# Pow-OR_v13-SFE-Pi.net
KiCad netlist of a schematic drawn in EAGLE
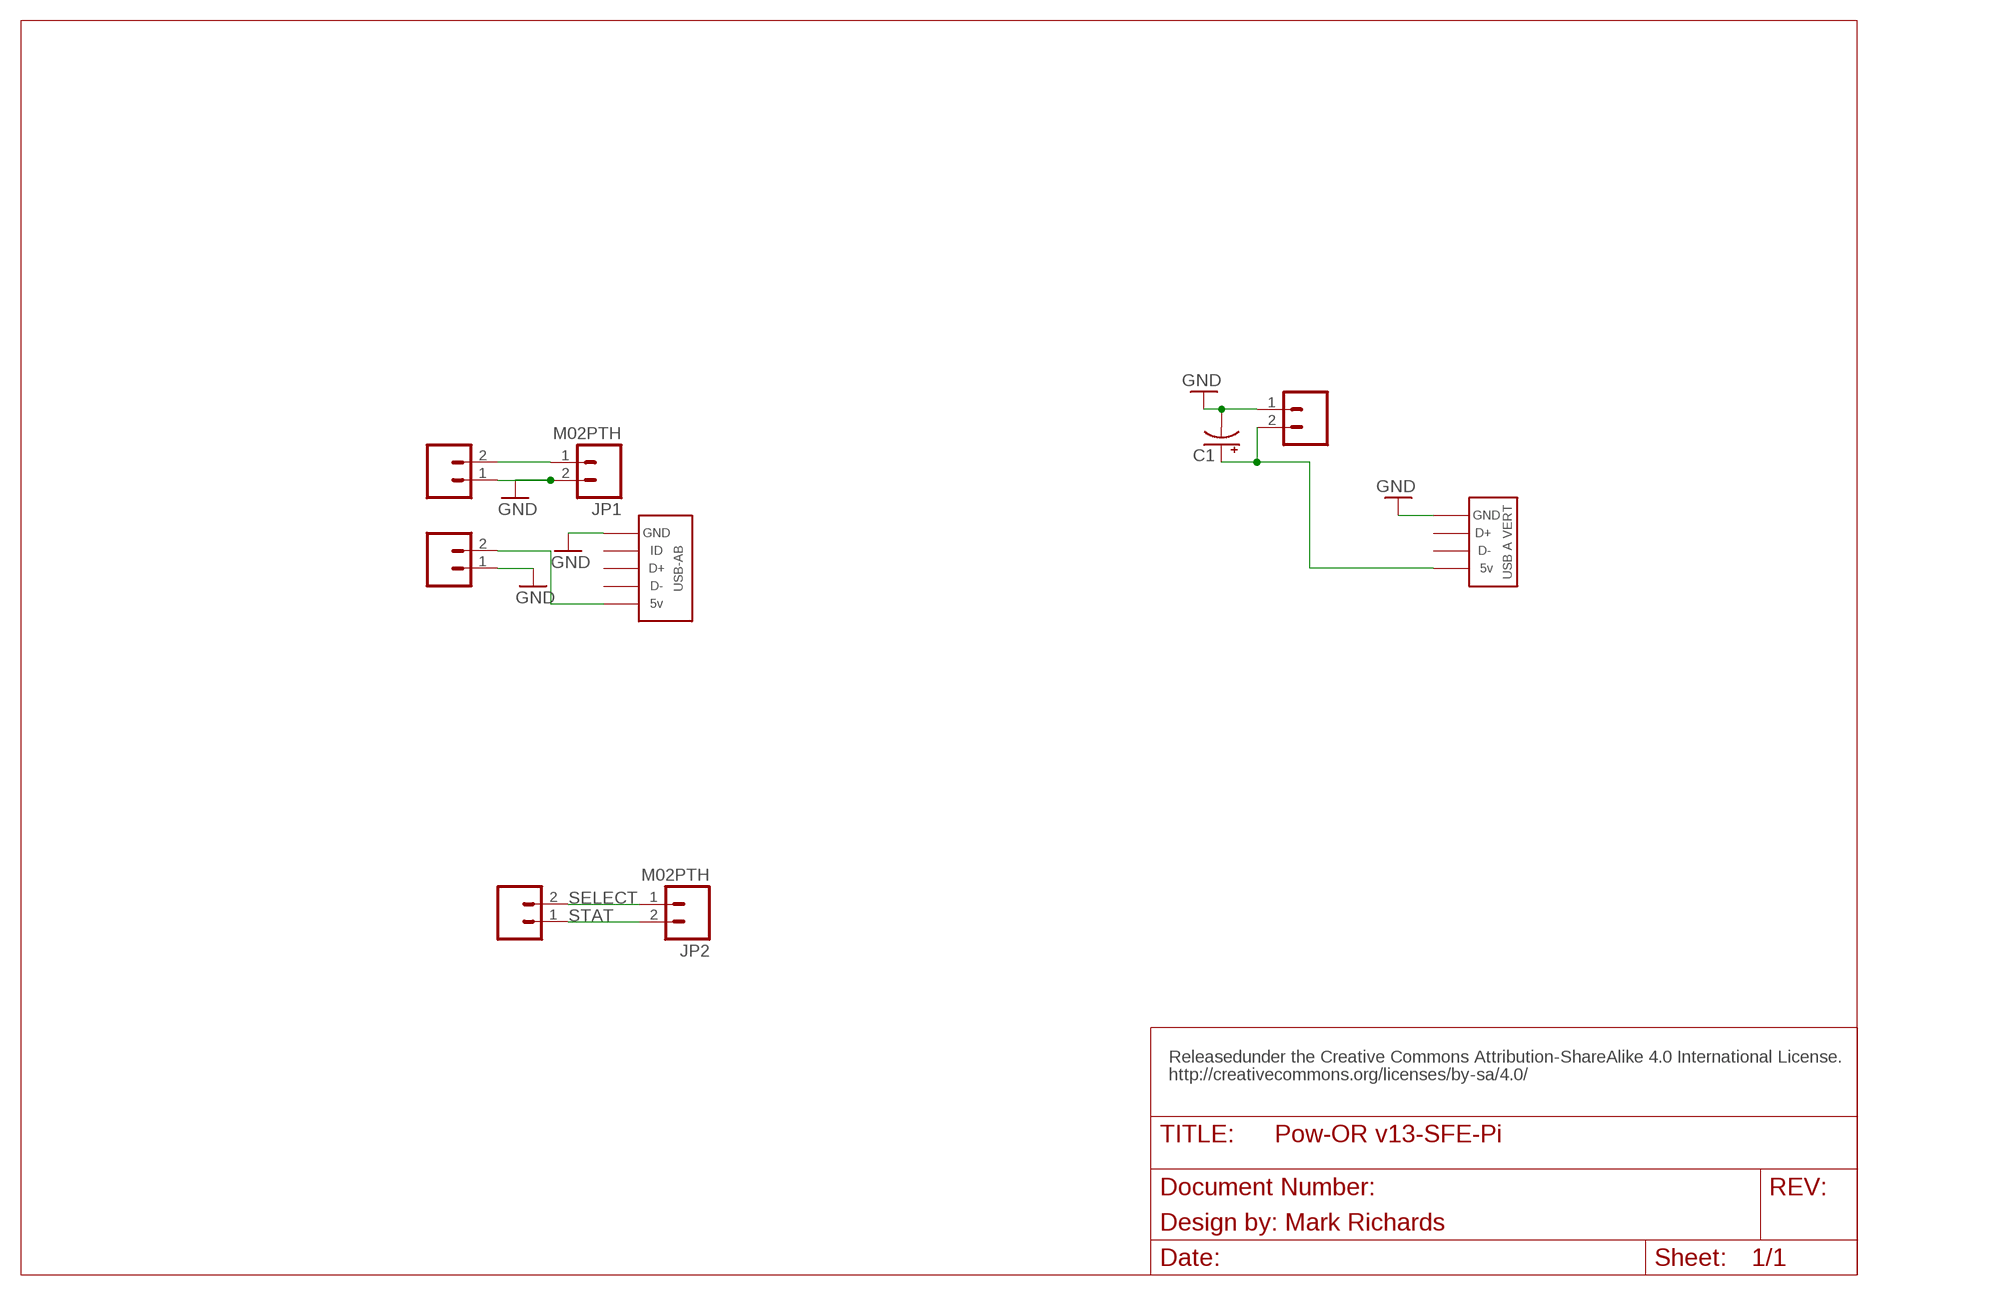
[diagram p0: schematic, sheet 1]

(export (version "E")
  (design (tool "Eeschema 10.0.6"))
  (components
    (comp (ref "C1")
      (value "CAP_POLPTH1")
      (footprint "eagle-import:CPOL-RADIAL-100UF-25V")
      (libsource (lib "eagle-import") (part "CAP_POLPTH1"))
    )
    (comp (ref "JP1")
      (value "M02PTH")
      (footprint "eagle-import:1X02")
      (libsource (lib "eagle-import") (part "M02PTH"))
    )
    (comp (ref "JP2")
      (value "M02PTH")
      (footprint "eagle-import:1X02")
      (libsource (lib "eagle-import") (part "M02PTH"))
    )
    (comp (ref "JP3")
      (value "M021X02_NO_SILK")
      (footprint "eagle-import:1X02_NO_SILK")
      (libsource (lib "eagle-import") (part "M021X02_NO_SILK"))
    )
    (comp (ref "JP4")
      (value "M021X02_NO_SILK")
      (footprint "eagle-import:1X02_NO_SILK")
      (libsource (lib "eagle-import") (part "M021X02_NO_SILK"))
    )
    (comp (ref "JP5")
      (value "M021X02_NO_SILK")
      (footprint "eagle-import:1X02_NO_SILK")
      (libsource (lib "eagle-import") (part "M021X02_NO_SILK"))
    )
    (comp (ref "JP6")
      (value "M021X02_NO_SILK")
      (footprint "eagle-import:1X02_NO_SILK")
      (libsource (lib "eagle-import") (part "M021X02_NO_SILK"))
    )
    (comp (ref "U$1")
      (value "USB-AB")
      (footprint "eagle-import:USB-AB")
      (libsource (lib "eagle-import") (part "USB-AB"))
    )
    (comp (ref "U$2")
      (value "USBA-VERT")
      (footprint "eagle-import:USBA-VERT")
      (libsource (lib "eagle-import") (part "USBA-VERT"))
    )
  )
  (nets
    (net (code "1") (name "/SELECT") (class "Default")
      (node (ref "JP2") (pin "1") (pinfunction "1_1") (pintype "passive"))
      (node (ref "JP5") (pin "2") (pinfunction "2_2") (pintype "passive"))
    )
    (net (code "2") (name "/STAT") (class "Default")
      (node (ref "JP2") (pin "2") (pinfunction "2_2") (pintype "passive"))
      (node (ref "JP5") (pin "1") (pinfunction "1_1") (pintype "passive"))
    )
    (net (code "3") (name "GND") (class "Default")
      (node (ref "C1") (pin "2") (pinfunction "-_2") (pintype "passive"))
      (node (ref "JP1") (pin "2") (pinfunction "2_2") (pintype "passive"))
      (node (ref "JP3") (pin "1") (pinfunction "1_1") (pintype "passive"))
      (node (ref "JP4") (pin "1") (pinfunction "1_1") (pintype "passive"))
      (node (ref "JP6") (pin "1") (pinfunction "1_1") (pintype "passive"))
      (node (ref "U$1") (pin "G") (pinfunction "G_G") (pintype "bidirectional"))
      (node (ref "U$2") (pin "NEG") (pinfunction "GND_NEG") (pintype "bidirectional"))
    )
    (net (code "4") (name "Net-(C1-+)") (class "Default")
      (node (ref "C1") (pin "1") (pinfunction "+_1") (pintype "passive"))
      (node (ref "JP6") (pin "2") (pinfunction "2_2") (pintype "passive"))
      (node (ref "U$2") (pin "VCC") (pinfunction "VCC_VCC") (pintype "bidirectional"))
    )
    (net (code "5") (name "Net-(JP1-Pad1)") (class "Default")
      (node (ref "JP1") (pin "1") (pinfunction "1_1") (pintype "passive"))
      (node (ref "JP3") (pin "2") (pinfunction "2_2") (pintype "passive"))
    )
    (net (code "6") (name "Net-(JP4-Pad2)") (class "Default")
      (node (ref "JP4") (pin "2") (pinfunction "2_2") (pintype "passive"))
      (node (ref "U$1") (pin "V") (pinfunction "V_V") (pintype "bidirectional"))
    )
    (net (code "7") (name "unconnected-(U$1-PadD+)") (class "Default")
      (node (ref "U$1") (pin "D+") (pinfunction "D+_D+") (pintype "bidirectional"))
    )
    (net (code "8") (name "unconnected-(U$1-PadD-)") (class "Default")
      (node (ref "U$1") (pin "D-") (pinfunction "D-_D-") (pintype "bidirectional"))
    )
    (net (code "9") (name "unconnected-(U$1-PadID)") (class "Default")
      (node (ref "U$1") (pin "ID") (pinfunction "ID_ID") (pintype "bidirectional"))
    )
    (net (code "10") (name "unconnected-(U$2-PadD+)") (class "Default")
      (node (ref "U$2") (pin "D+") (pinfunction "D+_D+") (pintype "bidirectional"))
    )
    (net (code "11") (name "unconnected-(U$2-PadD-)") (class "Default")
      (node (ref "U$2") (pin "D-") (pinfunction "D-_D-") (pintype "bidirectional"))
    )
  )
)
